# BATT_DISP_v6.net
KiCad netlist of a schematic drawn in EAGLE
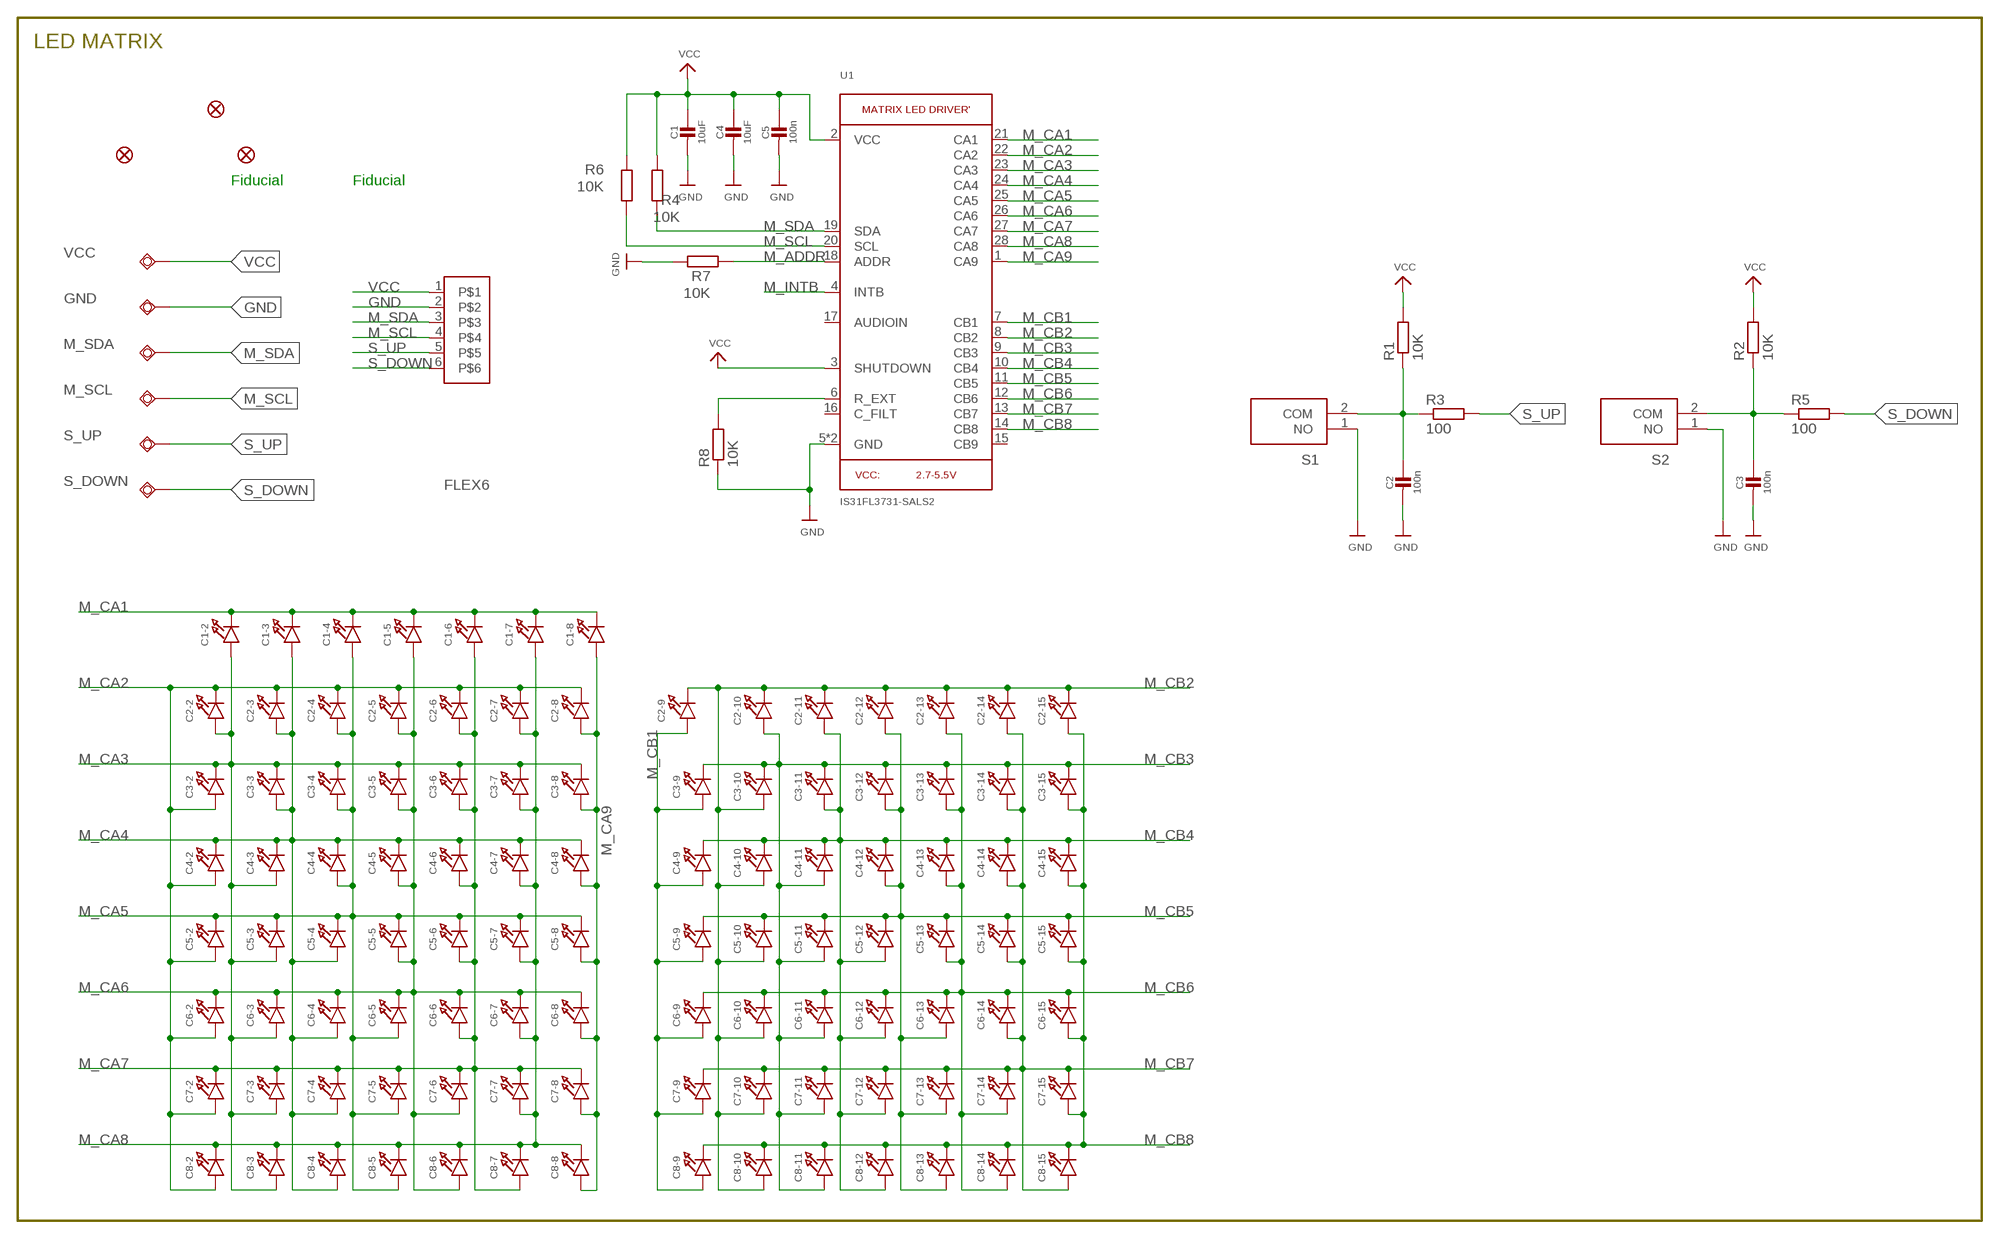
[diagram p0: schematic, sheet 1]

(export (version "E")
  (design (tool "Eeschema 10.0.6"))
  (components
    (comp (ref "C1")
      (value "10uF")
      (footprint "eagle-import:0805-NO")
      (libsource (lib "eagle-import") (part "CAP_CERAMIC0805-NOOUTLINE"))
    )
    (comp (ref "C1-2")
      (value "LED0402_NOOUTLINE")
      (footprint "eagle-import:CHIPLED_0402_NOOUTLINE")
      (libsource (lib "eagle-import") (part "LED0402_NOOUTLINE"))
    )
    (comp (ref "C1-3")
      (value "LED0402_NOOUTLINE")
      (footprint "eagle-import:CHIPLED_0402_NOOUTLINE")
      (libsource (lib "eagle-import") (part "LED0402_NOOUTLINE"))
    )
    (comp (ref "C1-4")
      (value "LED0402_NOOUTLINE")
      (footprint "eagle-import:CHIPLED_0402_NOOUTLINE")
      (libsource (lib "eagle-import") (part "LED0402_NOOUTLINE"))
    )
    (comp (ref "C1-5")
      (value "LED0402_NOOUTLINE")
      (footprint "eagle-import:CHIPLED_0402_NOOUTLINE")
      (libsource (lib "eagle-import") (part "LED0402_NOOUTLINE"))
    )
    (comp (ref "C1-6")
      (value "LED0402_NOOUTLINE")
      (footprint "eagle-import:CHIPLED_0402_NOOUTLINE")
      (libsource (lib "eagle-import") (part "LED0402_NOOUTLINE"))
    )
    (comp (ref "C1-7")
      (value "LED0402_NOOUTLINE")
      (footprint "eagle-import:CHIPLED_0402_NOOUTLINE")
      (libsource (lib "eagle-import") (part "LED0402_NOOUTLINE"))
    )
    (comp (ref "C1-8")
      (value "LED0402_NOOUTLINE")
      (footprint "eagle-import:CHIPLED_0402_NOOUTLINE")
      (libsource (lib "eagle-import") (part "LED0402_NOOUTLINE"))
    )
    (comp (ref "C2")
      (value "100n")
      (footprint "eagle-import:0805-NO")
      (libsource (lib "eagle-import") (part "CAP_CERAMIC0805-NOOUTLINE"))
    )
    (comp (ref "C2-2")
      (value "LED0402_NOOUTLINE")
      (footprint "eagle-import:CHIPLED_0402_NOOUTLINE")
      (libsource (lib "eagle-import") (part "LED0402_NOOUTLINE"))
    )
    (comp (ref "C2-3")
      (value "LED0402_NOOUTLINE")
      (footprint "eagle-import:CHIPLED_0402_NOOUTLINE")
      (libsource (lib "eagle-import") (part "LED0402_NOOUTLINE"))
    )
    (comp (ref "C2-4")
      (value "LED0402_NOOUTLINE")
      (footprint "eagle-import:CHIPLED_0402_NOOUTLINE")
      (libsource (lib "eagle-import") (part "LED0402_NOOUTLINE"))
    )
    (comp (ref "C2-5")
      (value "LED0402_NOOUTLINE")
      (footprint "eagle-import:CHIPLED_0402_NOOUTLINE")
      (libsource (lib "eagle-import") (part "LED0402_NOOUTLINE"))
    )
    (comp (ref "C2-6")
      (value "LED0402_NOOUTLINE")
      (footprint "eagle-import:CHIPLED_0402_NOOUTLINE")
      (libsource (lib "eagle-import") (part "LED0402_NOOUTLINE"))
    )
    (comp (ref "C2-7")
      (value "LED0402_NOOUTLINE")
      (footprint "eagle-import:CHIPLED_0402_NOOUTLINE")
      (libsource (lib "eagle-import") (part "LED0402_NOOUTLINE"))
    )
    (comp (ref "C2-8")
      (value "LED0402_NOOUTLINE")
      (footprint "eagle-import:CHIPLED_0402_NOOUTLINE")
      (libsource (lib "eagle-import") (part "LED0402_NOOUTLINE"))
    )
    (comp (ref "C2-9")
      (value "LED0402_NOOUTLINE")
      (footprint "eagle-import:CHIPLED_0402_NOOUTLINE")
      (libsource (lib "eagle-import") (part "LED0402_NOOUTLINE"))
    )
    (comp (ref "C2-10")
      (value "LED0402_NOOUTLINE")
      (footprint "eagle-import:CHIPLED_0402_NOOUTLINE")
      (libsource (lib "eagle-import") (part "LED0402_NOOUTLINE"))
    )
    (comp (ref "C2-11")
      (value "LED0402_NOOUTLINE")
      (footprint "eagle-import:CHIPLED_0402_NOOUTLINE")
      (libsource (lib "eagle-import") (part "LED0402_NOOUTLINE"))
    )
    (comp (ref "C2-12")
      (value "LED0402_NOOUTLINE")
      (footprint "eagle-import:CHIPLED_0402_NOOUTLINE")
      (libsource (lib "eagle-import") (part "LED0402_NOOUTLINE"))
    )
    (comp (ref "C2-13")
      (value "LED0402_NOOUTLINE")
      (footprint "eagle-import:CHIPLED_0402_NOOUTLINE")
      (libsource (lib "eagle-import") (part "LED0402_NOOUTLINE"))
    )
    (comp (ref "C2-14")
      (value "LED0402_NOOUTLINE")
      (footprint "eagle-import:CHIPLED_0402_NOOUTLINE")
      (libsource (lib "eagle-import") (part "LED0402_NOOUTLINE"))
    )
    (comp (ref "C2-15")
      (value "LED0402_NOOUTLINE")
      (footprint "eagle-import:CHIPLED_0402_NOOUTLINE")
      (libsource (lib "eagle-import") (part "LED0402_NOOUTLINE"))
    )
    (comp (ref "C3")
      (value "100n")
      (footprint "eagle-import:0805-NO")
      (libsource (lib "eagle-import") (part "CAP_CERAMIC0805-NOOUTLINE"))
    )
    (comp (ref "C3-2")
      (value "LED0402_NOOUTLINE")
      (footprint "eagle-import:CHIPLED_0402_NOOUTLINE")
      (libsource (lib "eagle-import") (part "LED0402_NOOUTLINE"))
    )
    (comp (ref "C3-3")
      (value "LED0402_NOOUTLINE")
      (footprint "eagle-import:CHIPLED_0402_NOOUTLINE")
      (libsource (lib "eagle-import") (part "LED0402_NOOUTLINE"))
    )
    (comp (ref "C3-4")
      (value "LED0402_NOOUTLINE")
      (footprint "eagle-import:CHIPLED_0402_NOOUTLINE")
      (libsource (lib "eagle-import") (part "LED0402_NOOUTLINE"))
    )
    (comp (ref "C3-5")
      (value "LED0402_NOOUTLINE")
      (footprint "eagle-import:CHIPLED_0402_NOOUTLINE")
      (libsource (lib "eagle-import") (part "LED0402_NOOUTLINE"))
    )
    (comp (ref "C3-6")
      (value "LED0402_NOOUTLINE")
      (footprint "eagle-import:CHIPLED_0402_NOOUTLINE")
      (libsource (lib "eagle-import") (part "LED0402_NOOUTLINE"))
    )
    (comp (ref "C3-7")
      (value "LED0402_NOOUTLINE")
      (footprint "eagle-import:CHIPLED_0402_NOOUTLINE")
      (libsource (lib "eagle-import") (part "LED0402_NOOUTLINE"))
    )
    (comp (ref "C3-8")
      (value "LED0402_NOOUTLINE")
      (footprint "eagle-import:CHIPLED_0402_NOOUTLINE")
      (libsource (lib "eagle-import") (part "LED0402_NOOUTLINE"))
    )
    (comp (ref "C3-9")
      (value "LED0402_NOOUTLINE")
      (footprint "eagle-import:CHIPLED_0402_NOOUTLINE")
      (libsource (lib "eagle-import") (part "LED0402_NOOUTLINE"))
    )
    (comp (ref "C3-10")
      (value "LED0402_NOOUTLINE")
      (footprint "eagle-import:CHIPLED_0402_NOOUTLINE")
      (libsource (lib "eagle-import") (part "LED0402_NOOUTLINE"))
    )
    (comp (ref "C3-11")
      (value "LED0402_NOOUTLINE")
      (footprint "eagle-import:CHIPLED_0402_NOOUTLINE")
      (libsource (lib "eagle-import") (part "LED0402_NOOUTLINE"))
    )
    (comp (ref "C3-12")
      (value "LED0402_NOOUTLINE")
      (footprint "eagle-import:CHIPLED_0402_NOOUTLINE")
      (libsource (lib "eagle-import") (part "LED0402_NOOUTLINE"))
    )
    (comp (ref "C3-13")
      (value "LED0402_NOOUTLINE")
      (footprint "eagle-import:CHIPLED_0402_NOOUTLINE")
      (libsource (lib "eagle-import") (part "LED0402_NOOUTLINE"))
    )
    (comp (ref "C3-14")
      (value "LED0402_NOOUTLINE")
      (footprint "eagle-import:CHIPLED_0402_NOOUTLINE")
      (libsource (lib "eagle-import") (part "LED0402_NOOUTLINE"))
    )
    (comp (ref "C3-15")
      (value "LED0402_NOOUTLINE")
      (footprint "eagle-import:CHIPLED_0402_NOOUTLINE")
      (libsource (lib "eagle-import") (part "LED0402_NOOUTLINE"))
    )
    (comp (ref "C4")
      (value "10uF")
      (footprint "eagle-import:0805-NO")
      (libsource (lib "eagle-import") (part "CAP_CERAMIC0805-NOOUTLINE"))
    )
    (comp (ref "C4-2")
      (value "LED0402_NOOUTLINE")
      (footprint "eagle-import:CHIPLED_0402_NOOUTLINE")
      (libsource (lib "eagle-import") (part "LED0402_NOOUTLINE"))
    )
    (comp (ref "C4-3")
      (value "LED0402_NOOUTLINE")
      (footprint "eagle-import:CHIPLED_0402_NOOUTLINE")
      (libsource (lib "eagle-import") (part "LED0402_NOOUTLINE"))
    )
    (comp (ref "C4-4")
      (value "LED0402_NOOUTLINE")
      (footprint "eagle-import:CHIPLED_0402_NOOUTLINE")
      (libsource (lib "eagle-import") (part "LED0402_NOOUTLINE"))
    )
    (comp (ref "C4-5")
      (value "LED0402_NOOUTLINE")
      (footprint "eagle-import:CHIPLED_0402_NOOUTLINE")
      (libsource (lib "eagle-import") (part "LED0402_NOOUTLINE"))
    )
    (comp (ref "C4-6")
      (value "LED0402_NOOUTLINE")
      (footprint "eagle-import:CHIPLED_0402_NOOUTLINE")
      (libsource (lib "eagle-import") (part "LED0402_NOOUTLINE"))
    )
    (comp (ref "C4-7")
      (value "LED0402_NOOUTLINE")
      (footprint "eagle-import:CHIPLED_0402_NOOUTLINE")
      (libsource (lib "eagle-import") (part "LED0402_NOOUTLINE"))
    )
    (comp (ref "C4-8")
      (value "LED0402_NOOUTLINE")
      (footprint "eagle-import:CHIPLED_0402_NOOUTLINE")
      (libsource (lib "eagle-import") (part "LED0402_NOOUTLINE"))
    )
    (comp (ref "C4-9")
      (value "LED0402_NOOUTLINE")
      (footprint "eagle-import:CHIPLED_0402_NOOUTLINE")
      (libsource (lib "eagle-import") (part "LED0402_NOOUTLINE"))
    )
    (comp (ref "C4-10")
      (value "LED0402_NOOUTLINE")
      (footprint "eagle-import:CHIPLED_0402_NOOUTLINE")
      (libsource (lib "eagle-import") (part "LED0402_NOOUTLINE"))
    )
    (comp (ref "C4-11")
      (value "LED0402_NOOUTLINE")
      (footprint "eagle-import:CHIPLED_0402_NOOUTLINE")
      (libsource (lib "eagle-import") (part "LED0402_NOOUTLINE"))
    )
    (comp (ref "C4-12")
      (value "LED0402_NOOUTLINE")
      (footprint "eagle-import:CHIPLED_0402_NOOUTLINE")
      (libsource (lib "eagle-import") (part "LED0402_NOOUTLINE"))
    )
    (comp (ref "C4-13")
      (value "LED0402_NOOUTLINE")
      (footprint "eagle-import:CHIPLED_0402_NOOUTLINE")
      (libsource (lib "eagle-import") (part "LED0402_NOOUTLINE"))
    )
    (comp (ref "C4-14")
      (value "LED0402_NOOUTLINE")
      (footprint "eagle-import:CHIPLED_0402_NOOUTLINE")
      (libsource (lib "eagle-import") (part "LED0402_NOOUTLINE"))
    )
    (comp (ref "C4-15")
      (value "LED0402_NOOUTLINE")
      (footprint "eagle-import:CHIPLED_0402_NOOUTLINE")
      (libsource (lib "eagle-import") (part "LED0402_NOOUTLINE"))
    )
    (comp (ref "C5")
      (value "100n")
      (footprint "eagle-import:0805-NO")
      (libsource (lib "eagle-import") (part "CAP_CERAMIC0805-NOOUTLINE"))
    )
    (comp (ref "C5-2")
      (value "LED0402_NOOUTLINE")
      (footprint "eagle-import:CHIPLED_0402_NOOUTLINE")
      (libsource (lib "eagle-import") (part "LED0402_NOOUTLINE"))
    )
    (comp (ref "C5-3")
      (value "LED0402_NOOUTLINE")
      (footprint "eagle-import:CHIPLED_0402_NOOUTLINE")
      (libsource (lib "eagle-import") (part "LED0402_NOOUTLINE"))
    )
    (comp (ref "C5-4")
      (value "LED0402_NOOUTLINE")
      (footprint "eagle-import:CHIPLED_0402_NOOUTLINE")
      (libsource (lib "eagle-import") (part "LED0402_NOOUTLINE"))
    )
    (comp (ref "C5-5")
      (value "LED0402_NOOUTLINE")
      (footprint "eagle-import:CHIPLED_0402_NOOUTLINE")
      (libsource (lib "eagle-import") (part "LED0402_NOOUTLINE"))
    )
    (comp (ref "C5-6")
      (value "LED0402_NOOUTLINE")
      (footprint "eagle-import:CHIPLED_0402_NOOUTLINE")
      (libsource (lib "eagle-import") (part "LED0402_NOOUTLINE"))
    )
    (comp (ref "C5-7")
      (value "LED0402_NOOUTLINE")
      (footprint "eagle-import:CHIPLED_0402_NOOUTLINE")
      (libsource (lib "eagle-import") (part "LED0402_NOOUTLINE"))
    )
    (comp (ref "C5-8")
      (value "LED0402_NOOUTLINE")
      (footprint "eagle-import:CHIPLED_0402_NOOUTLINE")
      (libsource (lib "eagle-import") (part "LED0402_NOOUTLINE"))
    )
    (comp (ref "C5-9")
      (value "LED0402_NOOUTLINE")
      (footprint "eagle-import:CHIPLED_0402_NOOUTLINE")
      (libsource (lib "eagle-import") (part "LED0402_NOOUTLINE"))
    )
    (comp (ref "C5-10")
      (value "LED0402_NOOUTLINE")
      (footprint "eagle-import:CHIPLED_0402_NOOUTLINE")
      (libsource (lib "eagle-import") (part "LED0402_NOOUTLINE"))
    )
    (comp (ref "C5-11")
      (value "LED0402_NOOUTLINE")
      (footprint "eagle-import:CHIPLED_0402_NOOUTLINE")
      (libsource (lib "eagle-import") (part "LED0402_NOOUTLINE"))
    )
    (comp (ref "C5-12")
      (value "LED0402_NOOUTLINE")
      (footprint "eagle-import:CHIPLED_0402_NOOUTLINE")
      (libsource (lib "eagle-import") (part "LED0402_NOOUTLINE"))
    )
    (comp (ref "C5-13")
      (value "LED0402_NOOUTLINE")
      (footprint "eagle-import:CHIPLED_0402_NOOUTLINE")
      (libsource (lib "eagle-import") (part "LED0402_NOOUTLINE"))
    )
    (comp (ref "C5-14")
      (value "LED0402_NOOUTLINE")
      (footprint "eagle-import:CHIPLED_0402_NOOUTLINE")
      (libsource (lib "eagle-import") (part "LED0402_NOOUTLINE"))
    )
    (comp (ref "C5-15")
      (value "LED0402_NOOUTLINE")
      (footprint "eagle-import:CHIPLED_0402_NOOUTLINE")
      (libsource (lib "eagle-import") (part "LED0402_NOOUTLINE"))
    )
    (comp (ref "C6-2")
      (value "LED0402_NOOUTLINE")
      (footprint "eagle-import:CHIPLED_0402_NOOUTLINE")
      (libsource (lib "eagle-import") (part "LED0402_NOOUTLINE"))
    )
    (comp (ref "C6-3")
      (value "LED0402_NOOUTLINE")
      (footprint "eagle-import:CHIPLED_0402_NOOUTLINE")
      (libsource (lib "eagle-import") (part "LED0402_NOOUTLINE"))
    )
    (comp (ref "C6-4")
      (value "LED0402_NOOUTLINE")
      (footprint "eagle-import:CHIPLED_0402_NOOUTLINE")
      (libsource (lib "eagle-import") (part "LED0402_NOOUTLINE"))
    )
    (comp (ref "C6-5")
      (value "LED0402_NOOUTLINE")
      (footprint "eagle-import:CHIPLED_0402_NOOUTLINE")
      (libsource (lib "eagle-import") (part "LED0402_NOOUTLINE"))
    )
    (comp (ref "C6-6")
      (value "LED0402_NOOUTLINE")
      (footprint "eagle-import:CHIPLED_0402_NOOUTLINE")
      (libsource (lib "eagle-import") (part "LED0402_NOOUTLINE"))
    )
    (comp (ref "C6-7")
      (value "LED0402_NOOUTLINE")
      (footprint "eagle-import:CHIPLED_0402_NOOUTLINE")
      (libsource (lib "eagle-import") (part "LED0402_NOOUTLINE"))
    )
    (comp (ref "C6-8")
      (value "LED0402_NOOUTLINE")
      (footprint "eagle-import:CHIPLED_0402_NOOUTLINE")
      (libsource (lib "eagle-import") (part "LED0402_NOOUTLINE"))
    )
    (comp (ref "C6-9")
      (value "LED0402_NOOUTLINE")
      (footprint "eagle-import:CHIPLED_0402_NOOUTLINE")
      (libsource (lib "eagle-import") (part "LED0402_NOOUTLINE"))
    )
    (comp (ref "C6-10")
      (value "LED0402_NOOUTLINE")
      (footprint "eagle-import:CHIPLED_0402_NOOUTLINE")
      (libsource (lib "eagle-import") (part "LED0402_NOOUTLINE"))
    )
    (comp (ref "C6-11")
      (value "LED0402_NOOUTLINE")
      (footprint "eagle-import:CHIPLED_0402_NOOUTLINE")
      (libsource (lib "eagle-import") (part "LED0402_NOOUTLINE"))
    )
    (comp (ref "C6-12")
      (value "LED0402_NOOUTLINE")
      (footprint "eagle-import:CHIPLED_0402_NOOUTLINE")
      (libsource (lib "eagle-import") (part "LED0402_NOOUTLINE"))
    )
    (comp (ref "C6-13")
      (value "LED0402_NOOUTLINE")
      (footprint "eagle-import:CHIPLED_0402_NOOUTLINE")
      (libsource (lib "eagle-import") (part "LED0402_NOOUTLINE"))
    )
    (comp (ref "C6-14")
      (value "LED0402_NOOUTLINE")
      (footprint "eagle-import:CHIPLED_0402_NOOUTLINE")
      (libsource (lib "eagle-import") (part "LED0402_NOOUTLINE"))
    )
    (comp (ref "C6-15")
      (value "LED0402_NOOUTLINE")
      (footprint "eagle-import:CHIPLED_0402_NOOUTLINE")
      (libsource (lib "eagle-import") (part "LED0402_NOOUTLINE"))
    )
    (comp (ref "C7-2")
      (value "LED0402_NOOUTLINE")
      (footprint "eagle-import:CHIPLED_0402_NOOUTLINE")
      (libsource (lib "eagle-import") (part "LED0402_NOOUTLINE"))
    )
    (comp (ref "C7-3")
      (value "LED0402_NOOUTLINE")
      (footprint "eagle-import:CHIPLED_0402_NOOUTLINE")
      (libsource (lib "eagle-import") (part "LED0402_NOOUTLINE"))
    )
    (comp (ref "C7-4")
      (value "LED0402_NOOUTLINE")
      (footprint "eagle-import:CHIPLED_0402_NOOUTLINE")
      (libsource (lib "eagle-import") (part "LED0402_NOOUTLINE"))
    )
    (comp (ref "C7-5")
      (value "LED0402_NOOUTLINE")
      (footprint "eagle-import:CHIPLED_0402_NOOUTLINE")
      (libsource (lib "eagle-import") (part "LED0402_NOOUTLINE"))
    )
    (comp (ref "C7-6")
      (value "LED0402_NOOUTLINE")
      (footprint "eagle-import:CHIPLED_0402_NOOUTLINE")
      (libsource (lib "eagle-import") (part "LED0402_NOOUTLINE"))
    )
    (comp (ref "C7-7")
      (value "LED0402_NOOUTLINE")
      (footprint "eagle-import:CHIPLED_0402_NOOUTLINE")
      (libsource (lib "eagle-import") (part "LED0402_NOOUTLINE"))
    )
    (comp (ref "C7-8")
      (value "LED0402_NOOUTLINE")
      (footprint "eagle-import:CHIPLED_0402_NOOUTLINE")
      (libsource (lib "eagle-import") (part "LED0402_NOOUTLINE"))
    )
    (comp (ref "C7-9")
      (value "LED0402_NOOUTLINE")
      (footprint "eagle-import:CHIPLED_0402_NOOUTLINE")
      (libsource (lib "eagle-import") (part "LED0402_NOOUTLINE"))
    )
    (comp (ref "C7-10")
      (value "LED0402_NOOUTLINE")
      (footprint "eagle-import:CHIPLED_0402_NOOUTLINE")
      (libsource (lib "eagle-import") (part "LED0402_NOOUTLINE"))
    )
    (comp (ref "C7-11")
      (value "LED0402_NOOUTLINE")
      (footprint "eagle-import:CHIPLED_0402_NOOUTLINE")
      (libsource (lib "eagle-import") (part "LED0402_NOOUTLINE"))
    )
    (comp (ref "C7-12")
      (value "LED0402_NOOUTLINE")
      (footprint "eagle-import:CHIPLED_0402_NOOUTLINE")
      (libsource (lib "eagle-import") (part "LED0402_NOOUTLINE"))
    )
    (comp (ref "C7-13")
      (value "LED0402_NOOUTLINE")
      (footprint "eagle-import:CHIPLED_0402_NOOUTLINE")
      (libsource (lib "eagle-import") (part "LED0402_NOOUTLINE"))
    )
    (comp (ref "C7-14")
      (value "LED0402_NOOUTLINE")
      (footprint "eagle-import:CHIPLED_0402_NOOUTLINE")
      (libsource (lib "eagle-import") (part "LED0402_NOOUTLINE"))
    )
    (comp (ref "C7-15")
      (value "LED0402_NOOUTLINE")
      (footprint "eagle-import:CHIPLED_0402_NOOUTLINE")
      (libsource (lib "eagle-import") (part "LED0402_NOOUTLINE"))
    )
    (comp (ref "C8-2")
      (value "LED0402_NOOUTLINE")
      (footprint "eagle-import:CHIPLED_0402_NOOUTLINE")
      (libsource (lib "eagle-import") (part "LED0402_NOOUTLINE"))
    )
    (comp (ref "C8-3")
      (value "LED0402_NOOUTLINE")
      (footprint "eagle-import:CHIPLED_0402_NOOUTLINE")
      (libsource (lib "eagle-import") (part "LED0402_NOOUTLINE"))
    )
    (comp (ref "C8-4")
      (value "LED0402_NOOUTLINE")
      (footprint "eagle-import:CHIPLED_0402_NOOUTLINE")
      (libsource (lib "eagle-import") (part "LED0402_NOOUTLINE"))
    )
    (comp (ref "C8-5")
      (value "LED0402_NOOUTLINE")
      (footprint "eagle-import:CHIPLED_0402_NOOUTLINE")
      (libsource (lib "eagle-import") (part "LED0402_NOOUTLINE"))
    )
    (comp (ref "C8-6")
      (value "LED0402_NOOUTLINE")
      (footprint "eagle-import:CHIPLED_0402_NOOUTLINE")
      (libsource (lib "eagle-import") (part "LED0402_NOOUTLINE"))
    )
    (comp (ref "C8-7")
      (value "LED0402_NOOUTLINE")
      (footprint "eagle-import:CHIPLED_0402_NOOUTLINE")
      (libsource (lib "eagle-import") (part "LED0402_NOOUTLINE"))
    )
    (comp (ref "C8-8")
      (value "LED0402_NOOUTLINE")
      (footprint "eagle-import:CHIPLED_0402_NOOUTLINE")
      (libsource (lib "eagle-import") (part "LED0402_NOOUTLINE"))
    )
    (comp (ref "C8-9")
      (value "LED0402_NOOUTLINE")
      (footprint "eagle-import:CHIPLED_0402_NOOUTLINE")
      (libsource (lib "eagle-import") (part "LED0402_NOOUTLINE"))
    )
    (comp (ref "C8-10")
      (value "LED0402_NOOUTLINE")
      (footprint "eagle-import:CHIPLED_0402_NOOUTLINE")
      (libsource (lib "eagle-import") (part "LED0402_NOOUTLINE"))
    )
    (comp (ref "C8-11")
      (value "LED0402_NOOUTLINE")
      (footprint "eagle-import:CHIPLED_0402_NOOUTLINE")
      (libsource (lib "eagle-import") (part "LED0402_NOOUTLINE"))
    )
    (comp (ref "C8-12")
      (value "LED0402_NOOUTLINE")
      (footprint "eagle-import:CHIPLED_0402_NOOUTLINE")
      (libsource (lib "eagle-import") (part "LED0402_NOOUTLINE"))
    )
    (comp (ref "C8-13")
      (value "LED0402_NOOUTLINE")
      (footprint "eagle-import:CHIPLED_0402_NOOUTLINE")
      (libsource (lib "eagle-import") (part "LED0402_NOOUTLINE"))
    )
    (comp (ref "C8-14")
      (value "LED0402_NOOUTLINE")
      (footprint "eagle-import:CHIPLED_0402_NOOUTLINE")
      (libsource (lib "eagle-import") (part "LED0402_NOOUTLINE"))
    )
    (comp (ref "C8-15")
      (value "LED0402_NOOUTLINE")
      (footprint "eagle-import:CHIPLED_0402_NOOUTLINE")
      (libsource (lib "eagle-import") (part "LED0402_NOOUTLINE"))
    )
    (comp (ref "FD1")
      (value "FIDUCIALUFIDUCIAL")
      (footprint "eagle-import:FIDUCIAL-MICRO")
      (libsource (lib "eagle-import") (part "FIDUCIALUFIDUCIAL"))
    )
    (comp (ref "FD2")
      (value "FIDUCIAL\"\"")
      (footprint "eagle-import:FIDUCIAL_1MM")
      (libsource (lib "eagle-import") (part "FIDUCIAL{dblquote}{dblquote}"))
    )
    (comp (ref "FD3")
      (value "FIDUCIAL\"\"")
      (footprint "eagle-import:FIDUCIAL_1MM")
      (libsource (lib "eagle-import") (part "FIDUCIAL{dblquote}{dblquote}"))
    )
    (comp (ref "GND")
      (value "TESTPAD_TPSQB1,27")
      (footprint "eagle-import:TESTPAD_B1,27")
      (libsource (lib "eagle-import") (part "TESTPAD_TPSQB1,27"))
    )
    (comp (ref "K1")
      (value "FLEX6")
      (footprint "eagle-import:FLEX6")
      (libsource (lib "eagle-import") (part "FLEX6"))
    )
    (comp (ref "M_SCL")
      (value "TESTPAD_TPSQB1,27")
      (footprint "eagle-import:TESTPAD_B1,27")
      (libsource (lib "eagle-import") (part "TESTPAD_TPSQB1,27"))
    )
    (comp (ref "M_SDA")
      (value "TESTPAD_TPSQB1,27")
      (footprint "eagle-import:TESTPAD_B1,27")
      (libsource (lib "eagle-import") (part "TESTPAD_TPSQB1,27"))
    )
    (comp (ref "R1")
      (value "10K")
      (footprint "eagle-import:R0603")
      (libsource (lib "eagle-import") (part "R-EU_R0603"))
    )
    (comp (ref "R2")
      (value "10K")
      (footprint "eagle-import:R0603")
      (libsource (lib "eagle-import") (part "R-EU_R0603"))
    )
    (comp (ref "R3")
      (value "100")
      (footprint "eagle-import:R0603")
      (libsource (lib "eagle-import") (part "R-EU_R0603"))
    )
    (comp (ref "R4")
      (value "10K")
      (footprint "eagle-import:R0603")
      (libsource (lib "eagle-import") (part "R-EU_R0603"))
    )
    (comp (ref "R5")
      (value "100")
      (footprint "eagle-import:R0603")
      (libsource (lib "eagle-import") (part "R-EU_R0603"))
    )
    (comp (ref "R6")
      (value "10K")
      (footprint "eagle-import:R0603")
      (libsource (lib "eagle-import") (part "R-EU_R0603"))
    )
    (comp (ref "R7")
      (value "10K")
      (footprint "eagle-import:R0603")
      (libsource (lib "eagle-import") (part "R-EU_R0603"))
    )
    (comp (ref "R8")
      (value "10K")
      (footprint "eagle-import:R0603")
      (libsource (lib "eagle-import") (part "R-EU_R0603"))
    )
    (comp (ref "S1")
      (value "KXT311LHS")
      (footprint "eagle-import:KXT311LHS")
      (fields (field (name "MOUSER_PART_NUMBER") "611-KXT311LHS"))
      (libsource (lib "eagle-import") (part "KXT311LHS"))
    )
    (comp (ref "S2")
      (value "KXT311LHS")
      (footprint "eagle-import:KXT311LHS")
      (fields (field (name "MOUSER_PART_NUMBER") "611-KXT311LHS"))
      (libsource (lib "eagle-import") (part "KXT311LHS"))
    )
    (comp (ref "S_DOWN")
      (value "TESTPAD_TPSQB1,27")
      (footprint "eagle-import:TESTPAD_B1,27")
      (libsource (lib "eagle-import") (part "TESTPAD_TPSQB1,27"))
    )
    (comp (ref "S_UP")
      (value "TESTPAD_TPSQB1,27")
      (footprint "eagle-import:TESTPAD_B1,27")
      (libsource (lib "eagle-import") (part "TESTPAD_TPSQB1,27"))
    )
    (comp (ref "U1")
      (value "IS31FL3731-SALS2")
      (footprint "eagle-import:QFN28_4MM_0.4MM")
      (libsource (lib "eagle-import") (part "IS31FL3731QFN"))
    )
    (comp (ref "VCC")
      (value "TESTPAD_TPSQB1,27")
      (footprint "eagle-import:TESTPAD_B1,27")
      (libsource (lib "eagle-import") (part "TESTPAD_TPSQB1,27"))
    )
  )
  (nets
    (net (code "1") (name "/M_ADDR") (class "Default")
      (node (ref "R7") (pin "1") (pinfunction "1_1") (pintype "passive"))
      (node (ref "U1") (pin "18") (pinfunction "ADDR_18") (pintype "bidirectional"))
    )
    (net (code "2") (name "/M_CA1") (class "Default")
      (node (ref "C1-2") (pin "C") (pinfunction "C_C") (pintype "passive"))
      (node (ref "C1-3") (pin "C") (pinfunction "C_C") (pintype "passive"))
      (node (ref "C1-4") (pin "C") (pinfunction "C_C") (pintype "passive"))
      (node (ref "C1-5") (pin "C") (pinfunction "C_C") (pintype "passive"))
      (node (ref "C1-6") (pin "C") (pinfunction "C_C") (pintype "passive"))
      (node (ref "C1-7") (pin "C") (pinfunction "C_C") (pintype "passive"))
      (node (ref "C1-8") (pin "C") (pinfunction "C_C") (pintype "passive"))
      (node (ref "U1") (pin "21") (pinfunction "CA1_21") (pintype "bidirectional"))
    )
    (net (code "3") (name "/M_CA2") (class "Default")
      (node (ref "C2-2") (pin "C") (pinfunction "C_C") (pintype "passive"))
      (node (ref "C2-3") (pin "C") (pinfunction "C_C") (pintype "passive"))
      (node (ref "C2-4") (pin "C") (pinfunction "C_C") (pintype "passive"))
      (node (ref "C2-5") (pin "C") (pinfunction "C_C") (pintype "passive"))
      (node (ref "C2-6") (pin "C") (pinfunction "C_C") (pintype "passive"))
      (node (ref "C2-7") (pin "C") (pinfunction "C_C") (pintype "passive"))
      (node (ref "C2-8") (pin "C") (pinfunction "C_C") (pintype "passive"))
      (node (ref "C3-2") (pin "A") (pinfunction "A_A") (pintype "passive"))
      (node (ref "C4-2") (pin "A") (pinfunction "A_A") (pintype "passive"))
      (node (ref "C5-2") (pin "A") (pinfunction "A_A") (pintype "passive"))
      (node (ref "C6-2") (pin "A") (pinfunction "A_A") (pintype "passive"))
      (node (ref "C7-2") (pin "A") (pinfunction "A_A") (pintype "passive"))
      (node (ref "C8-2") (pin "A") (pinfunction "A_A") (pintype "passive"))
      (node (ref "U1") (pin "22") (pinfunction "CA2_22") (pintype "bidirectional"))
    )
    (net (code "4") (name "/M_CA3") (class "Default")
      (node (ref "C1-2") (pin "A") (pinfunction "A_A") (pintype "passive"))
      (node (ref "C2-2") (pin "A") (pinfunction "A_A") (pintype "passive"))
      (node (ref "C3-2") (pin "C") (pinfunction "C_C") (pintype "passive"))
      (node (ref "C3-3") (pin "C") (pinfunction "C_C") (pintype "passive"))
      (node (ref "C3-4") (pin "C") (pinfunction "C_C") (pintype "passive"))
      (node (ref "C3-5") (pin "C") (pinfunction "C_C") (pintype "passive"))
      (node (ref "C3-6") (pin "C") (pinfunction "C_C") (pintype "passive"))
      (node (ref "C3-7") (pin "C") (pinfunction "C_C") (pintype "passive"))
      (node (ref "C3-8") (pin "C") (pinfunction "C_C") (pintype "passive"))
      (node (ref "C4-3") (pin "A") (pinfunction "A_A") (pintype "passive"))
      (node (ref "C5-3") (pin "A") (pinfunction "A_A") (pintype "passive"))
      (node (ref "C6-3") (pin "A") (pinfunction "A_A") (pintype "passive"))
      (node (ref "C7-3") (pin "A") (pinfunction "A_A") (pintype "passive"))
      (node (ref "C8-3") (pin "A") (pinfunction "A_A") (pintype "passive"))
      (node (ref "U1") (pin "23") (pinfunction "CA3_23") (pintype "bidirectional"))
    )
    (net (code "5") (name "/M_CA4") (class "Default")
      (node (ref "C1-3") (pin "A") (pinfunction "A_A") (pintype "passive"))
      (node (ref "C2-3") (pin "A") (pinfunction "A_A") (pintype "passive"))
      (node (ref "C3-3") (pin "A") (pinfunction "A_A") (pintype "passive"))
      (node (ref "C4-2") (pin "C") (pinfunction "C_C") (pintype "passive"))
      (node (ref "C4-3") (pin "C") (pinfunction "C_C") (pintype "passive"))
      (node (ref "C4-4") (pin "C") (pinfunction "C_C") (pintype "passive"))
      (node (ref "C4-5") (pin "C") (pinfunction "C_C") (pintype "passive"))
      (node (ref "C4-6") (pin "C") (pinfunction "C_C") (pintype "passive"))
      (node (ref "C4-7") (pin "C") (pinfunction "C_C") (pintype "passive"))
      (node (ref "C4-8") (pin "C") (pinfunction "C_C") (pintype "passive"))
      (node (ref "C5-4") (pin "A") (pinfunction "A_A") (pintype "passive"))
      (node (ref "C6-4") (pin "A") (pinfunction "A_A") (pintype "passive"))
      (node (ref "C7-4") (pin "A") (pinfunction "A_A") (pintype "passive"))
      (node (ref "C8-4") (pin "A") (pinfunction "A_A") (pintype "passive"))
      (node (ref "U1") (pin "24") (pinfunction "CA4_24") (pintype "bidirectional"))
    )
    (net (code "6") (name "/M_CA5") (class "Default")
      (node (ref "C1-4") (pin "A") (pinfunction "A_A") (pintype "passive"))
      (node (ref "C2-4") (pin "A") (pinfunction "A_A") (pintype "passive"))
      (node (ref "C3-4") (pin "A") (pinfunction "A_A") (pintype "passive"))
      (node (ref "C4-4") (pin "A") (pinfunction "A_A") (pintype "passive"))
      (node (ref "C5-2") (pin "C") (pinfunction "C_C") (pintype "passive"))
      (node (ref "C5-3") (pin "C") (pinfunction "C_C") (pintype "passive"))
      (node (ref "C5-4") (pin "C") (pinfunction "C_C") (pintype "passive"))
      (node (ref "C5-5") (pin "C") (pinfunction "C_C") (pintype "passive"))
      (node (ref "C5-6") (pin "C") (pinfunction "C_C") (pintype "passive"))
      (node (ref "C5-7") (pin "C") (pinfunction "C_C") (pintype "passive"))
      (node (ref "C5-8") (pin "C") (pinfunction "C_C") (pintype "passive"))
      (node (ref "C6-5") (pin "A") (pinfunction "A_A") (pintype "passive"))
      (node (ref "C7-5") (pin "A") (pinfunction "A_A") (pintype "passive"))
      (node (ref "C8-5") (pin "A") (pinfunction "A_A") (pintype "passive"))
      (node (ref "U1") (pin "25") (pinfunction "CA5_25") (pintype "bidirectional"))
    )
    (net (code "7") (name "/M_CA6") (class "Default")
      (node (ref "C1-5") (pin "A") (pinfunction "A_A") (pintype "passive"))
      (node (ref "C2-5") (pin "A") (pinfunction "A_A") (pintype "passive"))
      (node (ref "C3-5") (pin "A") (pinfunction "A_A") (pintype "passive"))
      (node (ref "C4-5") (pin "A") (pinfunction "A_A") (pintype "passive"))
      (node (ref "C5-5") (pin "A") (pinfunction "A_A") (pintype "passive"))
      (node (ref "C6-2") (pin "C") (pinfunction "C_C") (pintype "passive"))
      (node (ref "C6-3") (pin "C") (pinfunction "C_C") (pintype "passive"))
      (node (ref "C6-4") (pin "C") (pinfunction "C_C") (pintype "passive"))
      (node (ref "C6-5") (pin "C") (pinfunction "C_C") (pintype "passive"))
      (node (ref "C6-6") (pin "C") (pinfunction "C_C") (pintype "passive"))
      (node (ref "C6-7") (pin "C") (pinfunction "C_C") (pintype "passive"))
      (node (ref "C6-8") (pin "C") (pinfunction "C_C") (pintype "passive"))
      (node (ref "C7-6") (pin "A") (pinfunction "A_A") (pintype "passive"))
      (node (ref "C8-6") (pin "A") (pinfunction "A_A") (pintype "passive"))
      (node (ref "U1") (pin "26") (pinfunction "CA6_26") (pintype "bidirectional"))
    )
    (net (code "8") (name "/M_CA7") (class "Default")
      (node (ref "C1-6") (pin "A") (pinfunction "A_A") (pintype "passive"))
      (node (ref "C2-6") (pin "A") (pinfunction "A_A") (pintype "passive"))
      (node (ref "C3-6") (pin "A") (pinfunction "A_A") (pintype "passive"))
      (node (ref "C4-6") (pin "A") (pinfunction "A_A") (pintype "passive"))
      (node (ref "C5-6") (pin "A") (pinfunction "A_A") (pintype "passive"))
      (node (ref "C6-6") (pin "A") (pinfunction "A_A") (pintype "passive"))
      (node (ref "C7-2") (pin "C") (pinfunction "C_C") (pintype "passive"))
      (node (ref "C7-3") (pin "C") (pinfunction "C_C") (pintype "passive"))
      (node (ref "C7-4") (pin "C") (pinfunction "C_C") (pintype "passive"))
      (node (ref "C7-5") (pin "C") (pinfunction "C_C") (pintype "passive"))
      (node (ref "C7-6") (pin "C") (pinfunction "C_C") (pintype "passive"))
      (node (ref "C7-7") (pin "C") (pinfunction "C_C") (pintype "passive"))
      (node (ref "C7-8") (pin "C") (pinfunction "C_C") (pintype "passive"))
      (node (ref "C8-7") (pin "A") (pinfunction "A_A") (pintype "passive"))
      (node (ref "U1") (pin "27") (pinfunction "CA7_27") (pintype "bidirectional"))
    )
    (net (code "9") (name "/M_CA8") (class "Default")
      (node (ref "C1-7") (pin "A") (pinfunction "A_A") (pintype "passive"))
      (node (ref "C2-7") (pin "A") (pinfunction "A_A") (pintype "passive"))
      (node (ref "C3-7") (pin "A") (pinfunction "A_A") (pintype "passive"))
      (node (ref "C4-7") (pin "A") (pinfunction "A_A") (pintype "passive"))
      (node (ref "C5-7") (pin "A") (pinfunction "A_A") (pintype "passive"))
      (node (ref "C6-7") (pin "A") (pinfunction "A_A") (pintype "passive"))
      (node (ref "C7-7") (pin "A") (pinfunction "A_A") (pintype "passive"))
      (node (ref "C8-2") (pin "C") (pinfunction "C_C") (pintype "passive"))
      (node (ref "C8-3") (pin "C") (pinfunction "C_C") (pintype "passive"))
      (node (ref "C8-4") (pin "C") (pinfunction "C_C") (pintype "passive"))
      (node (ref "C8-5") (pin "C") (pinfunction "C_C") (pintype "passive"))
      (node (ref "C8-6") (pin "C") (pinfunction "C_C") (pintype "passive"))
      (node (ref "C8-7") (pin "C") (pinfunction "C_C") (pintype "passive"))
      (node (ref "C8-8") (pin "C") (pinfunction "C_C") (pintype "passive"))
      (node (ref "U1") (pin "28") (pinfunction "CA8_28") (pintype "bidirectional"))
    )
    (net (code "10") (name "/M_CA9") (class "Default")
      (node (ref "C1-8") (pin "A") (pinfunction "A_A") (pintype "passive"))
      (node (ref "C2-8") (pin "A") (pinfunction "A_A") (pintype "passive"))
      (node (ref "C3-8") (pin "A") (pinfunction "A_A") (pintype "passive"))
      (node (ref "C4-8") (pin "A") (pinfunction "A_A") (pintype "passive"))
      (node (ref "C5-8") (pin "A") (pinfunction "A_A") (pintype "passive"))
      (node (ref "C6-8") (pin "A") (pinfunction "A_A") (pintype "passive"))
      (node (ref "C7-8") (pin "A") (pinfunction "A_A") (pintype "passive"))
      (node (ref "C8-8") (pin "A") (pinfunction "A_A") (pintype "passive"))
      (node (ref "U1") (pin "1") (pinfunction "CA9_1") (pintype "bidirectional"))
    )
    (net (code "11") (name "/M_CB1") (class "Default")
      (node (ref "C2-9") (pin "A") (pinfunction "A_A") (pintype "passive"))
      (node (ref "C3-9") (pin "A") (pinfunction "A_A") (pintype "passive"))
      (node (ref "C4-9") (pin "A") (pinfunction "A_A") (pintype "passive"))
      (node (ref "C5-9") (pin "A") (pinfunction "A_A") (pintype "passive"))
      (node (ref "C6-9") (pin "A") (pinfunction "A_A") (pintype "passive"))
      (node (ref "C7-9") (pin "A") (pinfunction "A_A") (pintype "passive"))
      (node (ref "C8-9") (pin "A") (pinfunction "A_A") (pintype "passive"))
      (node (ref "U1") (pin "7") (pinfunction "CB1_7") (pintype "bidirectional"))
    )
    (net (code "12") (name "/M_CB2") (class "Default")
      (node (ref "C2-10") (pin "C") (pinfunction "C_C") (pintype "passive"))
      (node (ref "C2-11") (pin "C") (pinfunction "C_C") (pintype "passive"))
      (node (ref "C2-12") (pin "C") (pinfunction "C_C") (pintype "passive"))
      (node (ref "C2-13") (pin "C") (pinfunction "C_C") (pintype "passive"))
      (node (ref "C2-14") (pin "C") (pinfunction "C_C") (pintype "passive"))
      (node (ref "C2-15") (pin "C") (pinfunction "C_C") (pintype "passive"))
      (node (ref "C2-9") (pin "C") (pinfunction "C_C") (pintype "passive"))
      (node (ref "C3-10") (pin "A") (pinfunction "A_A") (pintype "passive"))
      (node (ref "C4-10") (pin "A") (pinfunction "A_A") (pintype "passive"))
      (node (ref "C5-10") (pin "A") (pinfunction "A_A") (pintype "passive"))
      (node (ref "C6-10") (pin "A") (pinfunction "A_A") (pintype "passive"))
      (node (ref "C7-10") (pin "A") (pinfunction "A_A") (pintype "passive"))
      (node (ref "C8-10") (pin "A") (pinfunction "A_A") (pintype "passive"))
      (node (ref "U1") (pin "8") (pinfunction "CB2_8") (pintype "bidirectional"))
    )
    (net (code "13") (name "/M_CB3") (class "Default")
      (node (ref "C2-10") (pin "A") (pinfunction "A_A") (pintype "passive"))
      (node (ref "C3-10") (pin "C") (pinfunction "C_C") (pintype "passive"))
      (node (ref "C3-11") (pin "C") (pinfunction "C_C") (pintype "passive"))
      (node (ref "C3-12") (pin "C") (pinfunction "C_C") (pintype "passive"))
      (node (ref "C3-13") (pin "C") (pinfunction "C_C") (pintype "passive"))
      (node (ref "C3-14") (pin "C") (pinfunction "C_C") (pintype "passive"))
      (node (ref "C3-15") (pin "C") (pinfunction "C_C") (pintype "passive"))
      (node (ref "C3-9") (pin "C") (pinfunction "C_C") (pintype "passive"))
      (node (ref "C4-11") (pin "A") (pinfunction "A_A") (pintype "passive"))
      (node (ref "C5-11") (pin "A") (pinfunction "A_A") (pintype "passive"))
      (node (ref "C6-11") (pin "A") (pinfunction "A_A") (pintype "passive"))
      (node (ref "C7-11") (pin "A") (pinfunction "A_A") (pintype "passive"))
      (node (ref "C8-11") (pin "A") (pinfunction "A_A") (pintype "passive"))
      (node (ref "U1") (pin "9") (pinfunction "CB3_9") (pintype "bidirectional"))
    )
    (net (code "14") (name "/M_CB4") (class "Default")
      (node (ref "C2-11") (pin "A") (pinfunction "A_A") (pintype "passive"))
      (node (ref "C3-11") (pin "A") (pinfunction "A_A") (pintype "passive"))
      (node (ref "C4-10") (pin "C") (pinfunction "C_C") (pintype "passive"))
      (node (ref "C4-11") (pin "C") (pinfunction "C_C") (pintype "passive"))
      (node (ref "C4-12") (pin "C") (pinfunction "C_C") (pintype "passive"))
      (node (ref "C4-13") (pin "C") (pinfunction "C_C") (pintype "passive"))
      (node (ref "C4-14") (pin "C") (pinfunction "C_C") (pintype "passive"))
      (node (ref "C4-15") (pin "C") (pinfunction "C_C") (pintype "passive"))
      (node (ref "C4-9") (pin "C") (pinfunction "C_C") (pintype "passive"))
      (node (ref "C5-12") (pin "A") (pinfunction "A_A") (pintype "passive"))
      (node (ref "C6-12") (pin "A") (pinfunction "A_A") (pintype "passive"))
      (node (ref "C7-12") (pin "A") (pinfunction "A_A") (pintype "passive"))
      (node (ref "C8-12") (pin "A") (pinfunction "A_A") (pintype "passive"))
      (node (ref "U1") (pin "10") (pinfunction "CB4_10") (pintype "bidirectional"))
    )
    (net (code "15") (name "/M_CB5") (class "Default")
      (node (ref "C2-12") (pin "A") (pinfunction "A_A") (pintype "passive"))
      (node (ref "C3-12") (pin "A") (pinfunction "A_A") (pintype "passive"))
      (node (ref "C4-12") (pin "A") (pinfunction "A_A") (pintype "passive"))
      (node (ref "C5-10") (pin "C") (pinfunction "C_C") (pintype "passive"))
      (node (ref "C5-11") (pin "C") (pinfunction "C_C") (pintype "passive"))
      (node (ref "C5-12") (pin "C") (pinfunction "C_C") (pintype "passive"))
      (node (ref "C5-13") (pin "C") (pinfunction "C_C") (pintype "passive"))
      (node (ref "C5-14") (pin "C") (pinfunction "C_C") (pintype "passive"))
      (node (ref "C5-15") (pin "C") (pinfunction "C_C") (pintype "passive"))
      (node (ref "C5-9") (pin "C") (pinfunction "C_C") (pintype "passive"))
      (node (ref "C6-13") (pin "A") (pinfunction "A_A") (pintype "passive"))
      (node (ref "C7-13") (pin "A") (pinfunction "A_A") (pintype "passive"))
      (node (ref "C8-13") (pin "A") (pinfunction "A_A") (pintype "passive"))
      (node (ref "U1") (pin "11") (pinfunction "CB5_11") (pintype "bidirectional"))
    )
    (net (code "16") (name "/M_CB6") (class "Default")
      (node (ref "C2-13") (pin "A") (pinfunction "A_A") (pintype "passive"))
      (node (ref "C3-13") (pin "A") (pinfunction "A_A") (pintype "passive"))
      (node (ref "C4-13") (pin "A") (pinfunction "A_A") (pintype "passive"))
      (node (ref "C5-13") (pin "A") (pinfunction "A_A") (pintype "passive"))
      (node (ref "C6-10") (pin "C") (pinfunction "C_C") (pintype "passive"))
      (node (ref "C6-11") (pin "C") (pinfunction "C_C") (pintype "passive"))
      (node (ref "C6-12") (pin "C") (pinfunction "C_C") (pintype "passive"))
      (node (ref "C6-13") (pin "C") (pinfunction "C_C") (pintype "passive"))
      (node (ref "C6-14") (pin "C") (pinfunction "C_C") (pintype "passive"))
      (node (ref "C6-15") (pin "C") (pinfunction "C_C") (pintype "passive"))
      (node (ref "C6-9") (pin "C") (pinfunction "C_C") (pintype "passive"))
      (node (ref "C7-14") (pin "A") (pinfunction "A_A") (pintype "passive"))
      (node (ref "C8-14") (pin "A") (pinfunction "A_A") (pintype "passive"))
      (node (ref "U1") (pin "12") (pinfunction "CB6_12") (pintype "bidirectional"))
    )
    (net (code "17") (name "/M_CB7") (class "Default")
      (node (ref "C2-14") (pin "A") (pinfunction "A_A") (pintype "passive"))
      (node (ref "C3-14") (pin "A") (pinfunction "A_A") (pintype "passive"))
      (node (ref "C4-14") (pin "A") (pinfunction "A_A") (pintype "passive"))
      (node (ref "C5-14") (pin "A") (pinfunction "A_A") (pintype "passive"))
      (node (ref "C6-14") (pin "A") (pinfunction "A_A") (pintype "passive"))
      (node (ref "C7-10") (pin "C") (pinfunction "C_C") (pintype "passive"))
      (node (ref "C7-11") (pin "C") (pinfunction "C_C") (pintype "passive"))
      (node (ref "C7-12") (pin "C") (pinfunction "C_C") (pintype "passive"))
      (node (ref "C7-13") (pin "C") (pinfunction "C_C") (pintype "passive"))
      (node (ref "C7-14") (pin "C") (pinfunction "C_C") (pintype "passive"))
      (node (ref "C7-15") (pin "C") (pinfunction "C_C") (pintype "passive"))
      (node (ref "C7-9") (pin "C") (pinfunction "C_C") (pintype "passive"))
      (node (ref "C8-15") (pin "A") (pinfunction "A_A") (pintype "passive"))
      (node (ref "U1") (pin "13") (pinfunction "CB7_13") (pintype "bidirectional"))
    )
    (net (code "18") (name "/M_CB8") (class "Default")
      (node (ref "C2-15") (pin "A") (pinfunction "A_A") (pintype "passive"))
      (node (ref "C3-15") (pin "A") (pinfunction "A_A") (pintype "passive"))
      (node (ref "C4-15") (pin "A") (pinfunction "A_A") (pintype "passive"))
      (node (ref "C5-15") (pin "A") (pinfunction "A_A") (pintype "passive"))
      (node (ref "C6-15") (pin "A") (pinfunction "A_A") (pintype "passive"))
      (node (ref "C7-15") (pin "A") (pinfunction "A_A") (pintype "passive"))
      (node (ref "C8-10") (pin "C") (pinfunction "C_C") (pintype "passive"))
      (node (ref "C8-11") (pin "C") (pinfunction "C_C") (pintype "passive"))
      (node (ref "C8-12") (pin "C") (pinfunction "C_C") (pintype "passive"))
      (node (ref "C8-13") (pin "C") (pinfunction "C_C") (pintype "passive"))
      (node (ref "C8-14") (pin "C") (pinfunction "C_C") (pintype "passive"))
      (node (ref "C8-15") (pin "C") (pinfunction "C_C") (pintype "passive"))
      (node (ref "C8-9") (pin "C") (pinfunction "C_C") (pintype "passive"))
      (node (ref "U1") (pin "14") (pinfunction "CB8_14") (pintype "bidirectional"))
    )
    (net (code "19") (name "/M_INTB") (class "Default")
      (node (ref "U1") (pin "4") (pinfunction "INTB_4") (pintype "output"))
    )
    (net (code "20") (name "GND") (class "Default")
      (node (ref "C1") (pin "2") (pinfunction "2_2") (pintype "passive"))
      (node (ref "C2") (pin "2") (pinfunction "2_2") (pintype "passive"))
      (node (ref "C3") (pin "2") (pinfunction "2_2") (pintype "passive"))
      (node (ref "C4") (pin "2") (pinfunction "2_2") (pintype "passive"))
      (node (ref "C5") (pin "2") (pinfunction "2_2") (pintype "passive"))
      (node (ref "GND") (pin "TP") (pinfunction "TP_TP") (pintype "input"))
      (node (ref "K1") (pin "2") (pinfunction "P$2_2") (pintype "bidirectional"))
      (node (ref "R7") (pin "2") (pinfunction "2_2") (pintype "passive"))
      (node (ref "R8") (pin "1") (pinfunction "1_1") (pintype "passive"))
      (node (ref "S1") (pin "1") (pinfunction "NO_1") (pintype "bidirectional"))
      (node (ref "S2") (pin "1") (pinfunction "NO_1") (pintype "bidirectional"))
      (node (ref "U1") (pin "5") (pinfunction "GND_5") (pintype "power_in"))
      (node (ref "U1") (pin "THERMAL") (pinfunction "GND_THERMAL") (pintype "power_in"))
    )
    (net (code "21") (name "M_SCL") (class "Default")
      (node (ref "K1") (pin "4") (pinfunction "P$4_4") (pintype "bidirectional"))
      (node (ref "M_SCL") (pin "TP") (pinfunction "TP_TP") (pintype "input"))
      (node (ref "R6") (pin "1") (pinfunction "1_1") (pintype "passive"))
      (node (ref "U1") (pin "20") (pinfunction "SCL_20") (pintype "bidirectional"))
    )
    (net (code "22") (name "M_SDA") (class "Default")
      (node (ref "K1") (pin "3") (pinfunction "P$3_3") (pintype "bidirectional"))
      (node (ref "M_SDA") (pin "TP") (pinfunction "TP_TP") (pintype "input"))
      (node (ref "R4") (pin "1") (pinfunction "1_1") (pintype "passive"))
      (node (ref "U1") (pin "19") (pinfunction "SDA_19") (pintype "bidirectional"))
    )
    (net (code "23") (name "Net-(S1-COM)") (class "Default")
      (node (ref "C2") (pin "1") (pinfunction "1_1") (pintype "passive"))
      (node (ref "R1") (pin "1") (pinfunction "1_1") (pintype "passive"))
      (node (ref "R3") (pin "1") (pinfunction "1_1") (pintype "passive"))
      (node (ref "S1") (pin "2") (pinfunction "COM_2") (pintype "bidirectional"))
    )
    (net (code "24") (name "Net-(S2-COM)") (class "Default")
      (node (ref "C3") (pin "1") (pinfunction "1_1") (pintype "passive"))
      (node (ref "R2") (pin "1") (pinfunction "1_1") (pintype "passive"))
      (node (ref "R5") (pin "1") (pinfunction "1_1") (pintype "passive"))
      (node (ref "S2") (pin "2") (pinfunction "COM_2") (pintype "bidirectional"))
    )
    (net (code "25") (name "Net-(U1-R_EXT)") (class "Default")
      (node (ref "R8") (pin "2") (pinfunction "2_2") (pintype "passive"))
      (node (ref "U1") (pin "6") (pinfunction "R_EXT_6") (pintype "bidirectional"))
    )
    (net (code "26") (name "S_DOWN") (class "Default")
      (node (ref "K1") (pin "6") (pinfunction "P$6_6") (pintype "bidirectional"))
      (node (ref "R5") (pin "2") (pinfunction "2_2") (pintype "passive"))
      (node (ref "S_DOWN") (pin "TP") (pinfunction "TP_TP") (pintype "input"))
    )
    (net (code "27") (name "S_UP") (class "Default")
      (node (ref "K1") (pin "5") (pinfunction "P$5_5") (pintype "bidirectional"))
      (node (ref "R3") (pin "2") (pinfunction "2_2") (pintype "passive"))
      (node (ref "S_UP") (pin "TP") (pinfunction "TP_TP") (pintype "input"))
    )
    (net (code "28") (name "VCC") (class "Default")
      (node (ref "C1") (pin "1") (pinfunction "1_1") (pintype "passive"))
      (node (ref "C4") (pin "1") (pinfunction "1_1") (pintype "passive"))
      (node (ref "C5") (pin "1") (pinfunction "1_1") (pintype "passive"))
      (node (ref "K1") (pin "1") (pinfunction "P$1_1") (pintype "bidirectional"))
      (node (ref "R1") (pin "2") (pinfunction "2_2") (pintype "passive"))
      (node (ref "R2") (pin "2") (pinfunction "2_2") (pintype "passive"))
      (node (ref "R4") (pin "2") (pinfunction "2_2") (pintype "passive"))
      (node (ref "R6") (pin "2") (pinfunction "2_2") (pintype "passive"))
      (node (ref "U1") (pin "2") (pinfunction "VCC_2") (pintype "power_in"))
      (node (ref "U1") (pin "3") (pinfunction "SHUTDOWN_3") (pintype "input"))
      (node (ref "VCC") (pin "TP") (pinfunction "TP_TP") (pintype "input"))
    )
    (net (code "29") (name "unconnected-(U1-AUDIOIN-Pad17)") (class "Default")
      (node (ref "U1") (pin "17") (pinfunction "AUDIOIN_17") (pintype "input"))
    )
    (net (code "30") (name "unconnected-(U1-CB9-Pad15)") (class "Default")
      (node (ref "U1") (pin "15") (pinfunction "CB9_15") (pintype "bidirectional"))
    )
    (net (code "31") (name "unconnected-(U1-C_FILT-Pad16)") (class "Default")
      (node (ref "U1") (pin "16") (pinfunction "C_FILT_16") (pintype "bidirectional"))
    )
  )
)
